# CDST_final_PCB_v1_0.net
KiCad netlist of a schematic drawn in EAGLE
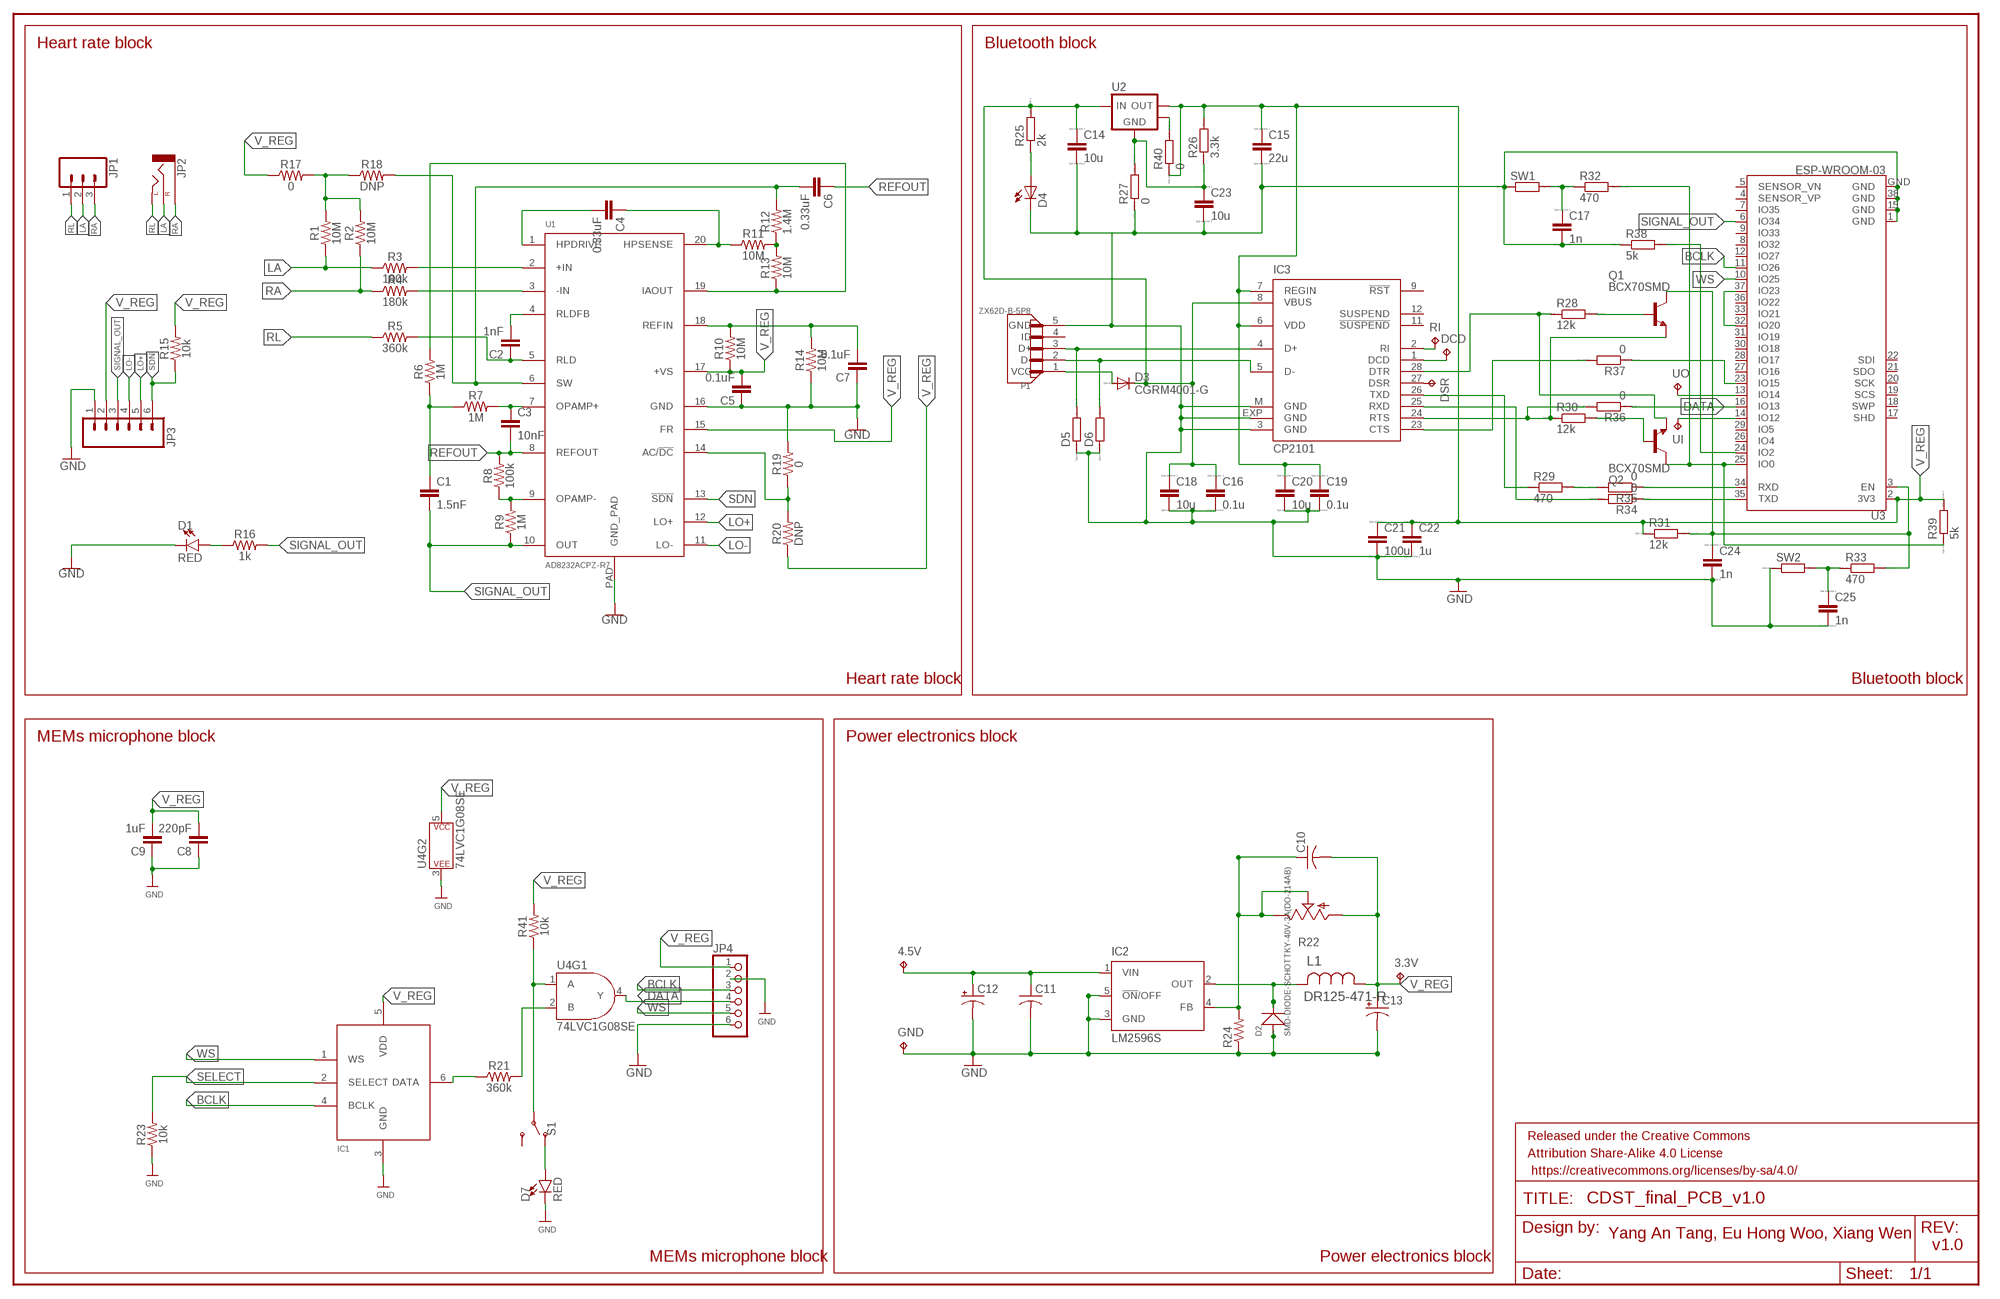
[diagram p0: schematic, sheet 1]

(export (version "E")
  (design (tool "Eeschema 10.0.6"))
  (components
    (comp (ref "3.3V")
      (value "TPTP20SQ")
      (footprint "eagle-import:TP20SQ")
      (libsource (lib "eagle-import") (part "TPTP20SQ"))
    )
    (comp (ref "4.5V")
      (value "TPTP20SQ")
      (footprint "eagle-import:TP20SQ")
      (libsource (lib "eagle-import") (part "TPTP20SQ"))
    )
    (comp (ref "C1")
      (value "1.5nF")
      (footprint "eagle-import:C1206")
      (libsource (lib "eagle-import") (part "C-EUC1206"))
    )
    (comp (ref "C2")
      (value "1nF")
      (footprint "eagle-import:C1206")
      (libsource (lib "eagle-import") (part "C-EUC1206"))
    )
    (comp (ref "C3")
      (value "10nF")
      (footprint "eagle-import:C1206")
      (libsource (lib "eagle-import") (part "C-EUC1206"))
    )
    (comp (ref "C4")
      (value "0.33uF")
      (footprint "eagle-import:C1206")
      (libsource (lib "eagle-import") (part "C-EUC1206"))
    )
    (comp (ref "C5")
      (value "0.1uF")
      (footprint "eagle-import:C1206")
      (libsource (lib "eagle-import") (part "C-EUC1206"))
    )
    (comp (ref "C6")
      (value "0.33uF")
      (footprint "eagle-import:C1206")
      (libsource (lib "eagle-import") (part "C-EUC1206"))
    )
    (comp (ref "C7")
      (value "0.1uF")
      (footprint "eagle-import:C1206")
      (libsource (lib "eagle-import") (part "C-EUC1206"))
    )
    (comp (ref "C8")
      (value "220pF")
      (footprint "eagle-import:C1206")
      (libsource (lib "eagle-import") (part "C-EUC1206"))
    )
    (comp (ref "C9")
      (value "1uF")
      (footprint "eagle-import:C1206")
      (libsource (lib "eagle-import") (part "C-EUC1206"))
    )
    (comp (ref "C10")
      (value "C-USC0402")
      (footprint "eagle-import:C0402")
      (libsource (lib "eagle-import") (part "C-USC0402"))
    )
    (comp (ref "C11")
      (value "C-USC0402")
      (footprint "eagle-import:C0402")
      (libsource (lib "eagle-import") (part "C-USC0402"))
    )
    (comp (ref "C12")
      (value "CPOL-USSANYO_SMD_F8")
      (footprint "eagle-import:SANYO-OSCON_SMD_F8")
      (libsource (lib "eagle-import") (part "CPOL-USSANYO_SMD_F8"))
    )
    (comp (ref "C13")
      (value "CPOL-USSANYO_SMD_F8")
      (footprint "eagle-import:SANYO-OSCON_SMD_F8")
      (libsource (lib "eagle-import") (part "CPOL-USSANYO_SMD_F8"))
    )
    (comp (ref "C14")
      (value "10u")
      (footprint "eagle-import:C1206")
      (libsource (lib "eagle-import") (part "CC1206"))
    )
    (comp (ref "C15")
      (value "22u")
      (footprint "eagle-import:C1206")
      (libsource (lib "eagle-import") (part "CC1206"))
    )
    (comp (ref "C16")
      (value "0.1u")
      (footprint "eagle-import:C1206")
      (libsource (lib "eagle-import") (part "CC1206"))
    )
    (comp (ref "C17")
      (value "1n")
      (footprint "eagle-import:C1206")
      (libsource (lib "eagle-import") (part "CC1206"))
    )
    (comp (ref "C18")
      (value "10u")
      (footprint "eagle-import:C1206")
      (libsource (lib "eagle-import") (part "CC1206"))
    )
    (comp (ref "C19")
      (value "0.1u")
      (footprint "eagle-import:C1206")
      (libsource (lib "eagle-import") (part "CC1206"))
    )
    (comp (ref "C20")
      (value "10u")
      (footprint "eagle-import:C1206")
      (libsource (lib "eagle-import") (part "CC1206"))
    )
    (comp (ref "C21")
      (value "100u")
      (footprint "eagle-import:C1206")
      (libsource (lib "eagle-import") (part "CC1206"))
    )
    (comp (ref "C22")
      (value "1u")
      (footprint "eagle-import:C1206")
      (libsource (lib "eagle-import") (part "CC1206"))
    )
    (comp (ref "C23")
      (value "10u")
      (footprint "eagle-import:C1206")
      (libsource (lib "eagle-import") (part "CC1206"))
    )
    (comp (ref "C24")
      (value "1n")
      (footprint "eagle-import:C1206")
      (libsource (lib "eagle-import") (part "CC1206"))
    )
    (comp (ref "C25")
      (value "1n")
      (footprint "eagle-import:C1206")
      (libsource (lib "eagle-import") (part "CC1206"))
    )
    (comp (ref "D1")
      (value "RED")
      (footprint "eagle-import:LED-1206")
      (libsource (lib "eagle-import") (part "LED-RED1206"))
    )
    (comp (ref "D2")
      (value "SMD-DIODE-SCHOTTKY-40V-3A(DO-214AB)")
      (footprint "eagle-import:DO-214AB")
      (fields (field (name "MF") "Vishay") (field (name "MP") "SS34-E3/57T"))
      (libsource (lib "eagle-import") (part "SMD-DIODE-SCHOTTKY-40V-3A(DO-214AB)"))
    )
    (comp (ref "D3")
      (value "CGRM4001-G")
      (footprint "eagle-import:SOD-123_MINI-SMA")
      (libsource (lib "eagle-import") (part "CGRM400-G1"))
    )
    (comp (ref "D4")
      (value "LEDCHIPLED_0805")
      (footprint "eagle-import:CHIPLED_0805")
      (libsource (lib "eagle-import") (part "LEDCHIPLED_0805"))
    )
    (comp (ref "D5")
      (value "RR0402")
      (footprint "eagle-import:R0402")
      (libsource (lib "eagle-import") (part "RR0402"))
    )
    (comp (ref "D6")
      (value "RR0402")
      (footprint "eagle-import:R0402")
      (libsource (lib "eagle-import") (part "RR0402"))
    )
    (comp (ref "D7")
      (value "RED")
      (footprint "eagle-import:LED-1206")
      (libsource (lib "eagle-import") (part "LED-RED1206"))
    )
    (comp (ref "DCD")
      (value "TPB2,54")
      (footprint "eagle-import:B2,54")
      (libsource (lib "eagle-import") (part "testpad_385_TPB2,54"))
    )
    (comp (ref "DSR")
      (value "TPB2,54")
      (footprint "eagle-import:B2,54")
      (libsource (lib "eagle-import") (part "testpad_385_TPB2,54"))
    )
    (comp (ref "FRAME1")
      (value "FRAME-LEDGER")
      (footprint "eagle-import:CREATIVE_COMMONS")
      (libsource (lib "eagle-import") (part "FRAME-LEDGER"))
    )
    (comp (ref "GND")
      (value "TPTP20SQ")
      (footprint "eagle-import:TP20SQ")
      (libsource (lib "eagle-import") (part "TPTP20SQ"))
    )
    (comp (ref "IC1")
      (value "MIC_I2S_SPH0645")
      (footprint "eagle-import:SPH0645LM4H")
      (libsource (lib "eagle-import") (part "MIC_I2S_SPH0645"))
    )
    (comp (ref "IC2")
      (value "LM2596S")
      (footprint "eagle-import:TO263-5")
      (fields (field (name "MF") "NATIONAL SEMICONDUCTOR") (field (name "MPN") "LM2596S-ADJ/NOPB"))
      (libsource (lib "eagle-import") (part "LM2596S"))
    )
    (comp (ref "IC3")
      (value "CP2101")
      (footprint "eagle-import:MLP28")
      (fields (field (name "MF") "FARNELL") (field (name "MPN") "CP2102-GM"))
      (libsource (lib "eagle-import") (part "CP2101"))
    )
    (comp (ref "JP1")
      (value "M03PTH")
      (footprint "eagle-import:1X03")
      (libsource (lib "eagle-import") (part "M03PTH"))
    )
    (comp (ref "JP2")
      (value "AUDIO-JACKSMD2")
      (footprint "eagle-import:AUDIO-JACK-3.5MM-SMD")
      (libsource (lib "eagle-import") (part "AUDIO-JACKSMD2"))
    )
    (comp (ref "JP3")
      (value "M06SIP")
      (footprint "eagle-import:1X06")
      (libsource (lib "eagle-import") (part "M06SIP"))
    )
    (comp (ref "JP4")
      (value "HEADER-1X6ROUND")
      (footprint "eagle-import:1X06_ROUND")
      (libsource (lib "eagle-import") (part "HEADER-1X6ROUND"))
    )
    (comp (ref "L1")
      (value "DR125-471-R")
      (footprint "eagle-import:INDM125125X600N")
      (fields (field (name "MF") "Cooper Bussmann"))
      (libsource (lib "eagle-import") (part "DR125-471-R"))
    )
    (comp (ref "P1")
      (value "ZX62D-B-5P8")
      (footprint "eagle-import:HRS_ZX62D-B-5P8")
      (fields (field (name "MF") "Hirose"))
      (libsource (lib "eagle-import") (part "ZX62D-B-5P8"))
    )
    (comp (ref "Q1")
      (value "BCX70SMD")
      (footprint "eagle-import:SOT23")
      (libsource (lib "eagle-import") (part "BCX70SMD"))
    )
    (comp (ref "Q2")
      (value "BCX70SMD")
      (footprint "eagle-import:SOT23")
      (libsource (lib "eagle-import") (part "BCX70SMD"))
    )
    (comp (ref "R1")
      (value "10M")
      (footprint "eagle-import:1206")
      (libsource (lib "eagle-import") (part "RESISTOR1206"))
    )
    (comp (ref "R2")
      (value "10M")
      (footprint "eagle-import:1206")
      (libsource (lib "eagle-import") (part "RESISTOR1206"))
    )
    (comp (ref "R3")
      (value "180k")
      (footprint "eagle-import:1206")
      (libsource (lib "eagle-import") (part "RESISTOR1206"))
    )
    (comp (ref "R4")
      (value "180k")
      (footprint "eagle-import:1206")
      (libsource (lib "eagle-import") (part "RESISTOR1206"))
    )
    (comp (ref "R5")
      (value "360k")
      (footprint "eagle-import:1206")
      (libsource (lib "eagle-import") (part "RESISTOR1206"))
    )
    (comp (ref "R6")
      (value "1M")
      (footprint "eagle-import:1206")
      (libsource (lib "eagle-import") (part "RESISTOR1206"))
    )
    (comp (ref "R7")
      (value "1M")
      (footprint "eagle-import:1206")
      (libsource (lib "eagle-import") (part "RESISTOR1206"))
    )
    (comp (ref "R8")
      (value "100k")
      (footprint "eagle-import:1206")
      (libsource (lib "eagle-import") (part "RESISTOR1206"))
    )
    (comp (ref "R9")
      (value "1M")
      (footprint "eagle-import:1206")
      (libsource (lib "eagle-import") (part "RESISTOR1206"))
    )
    (comp (ref "R10")
      (value "10M")
      (footprint "eagle-import:1206")
      (libsource (lib "eagle-import") (part "RESISTOR1206"))
    )
    (comp (ref "R11")
      (value "10M")
      (footprint "eagle-import:1206")
      (libsource (lib "eagle-import") (part "RESISTOR1206"))
    )
    (comp (ref "R12")
      (value "1.4M")
      (footprint "eagle-import:1206")
      (libsource (lib "eagle-import") (part "RESISTOR1206"))
    )
    (comp (ref "R13")
      (value "10M")
      (footprint "eagle-import:1206")
      (libsource (lib "eagle-import") (part "RESISTOR1206"))
    )
    (comp (ref "R14")
      (value "10M")
      (footprint "eagle-import:1206")
      (libsource (lib "eagle-import") (part "RESISTOR1206"))
    )
    (comp (ref "R15")
      (value "10k")
      (footprint "eagle-import:1206")
      (libsource (lib "eagle-import") (part "RESISTOR1206"))
    )
    (comp (ref "R16")
      (value "1k")
      (footprint "eagle-import:1206")
      (libsource (lib "eagle-import") (part "RESISTOR1206"))
    )
    (comp (ref "R17")
      (value "0")
      (footprint "eagle-import:1206")
      (libsource (lib "eagle-import") (part "RESISTOR1206"))
    )
    (comp (ref "R18")
      (value "DNP")
      (footprint "eagle-import:1206")
      (libsource (lib "eagle-import") (part "RESISTOR1206"))
    )
    (comp (ref "R19")
      (value "0")
      (footprint "eagle-import:1206")
      (libsource (lib "eagle-import") (part "RESISTOR1206"))
    )
    (comp (ref "R20")
      (value "DNP")
      (footprint "eagle-import:1206")
      (libsource (lib "eagle-import") (part "RESISTOR1206"))
    )
    (comp (ref "R21")
      (value "360k")
      (footprint "eagle-import:1206")
      (libsource (lib "eagle-import") (part "RESISTOR1206"))
    )
    (comp (ref "R22")
      (value "TRIM_US-RJ9W")
      (footprint "eagle-import:RJ9W")
      (libsource (lib "eagle-import") (part "TRIM_US-RJ9W"))
    )
    (comp (ref "R23")
      (value "10k")
      (footprint "eagle-import:1206")
      (libsource (lib "eagle-import") (part "RESISTOR1206"))
    )
    (comp (ref "R24")
      (value "R-US_MELF0204W")
      (footprint "eagle-import:MINI_MELF-0204W")
      (libsource (lib "eagle-import") (part "R-US_MELF0204W"))
    )
    (comp (ref "R25")
      (value "2k")
      (footprint "eagle-import:R1206")
      (libsource (lib "eagle-import") (part "RR1206"))
    )
    (comp (ref "R26")
      (value "3.3k")
      (footprint "eagle-import:R1206")
      (libsource (lib "eagle-import") (part "RR1206"))
    )
    (comp (ref "R27")
      (value "0")
      (footprint "eagle-import:R1206")
      (libsource (lib "eagle-import") (part "RR1206"))
    )
    (comp (ref "R28")
      (value "12k")
      (footprint "eagle-import:R1206")
      (libsource (lib "eagle-import") (part "RR1206"))
    )
    (comp (ref "R29")
      (value "470")
      (footprint "eagle-import:R1206")
      (libsource (lib "eagle-import") (part "RR1206"))
    )
    (comp (ref "R30")
      (value "12k")
      (footprint "eagle-import:R1206")
      (libsource (lib "eagle-import") (part "RR1206"))
    )
    (comp (ref "R31")
      (value "12k")
      (footprint "eagle-import:R1206")
      (libsource (lib "eagle-import") (part "RR1206"))
    )
    (comp (ref "R32")
      (value "470")
      (footprint "eagle-import:R1206")
      (libsource (lib "eagle-import") (part "RR1206"))
    )
    (comp (ref "R33")
      (value "470")
      (footprint "eagle-import:R1206")
      (libsource (lib "eagle-import") (part "RR1206"))
    )
    (comp (ref "R34")
      (value "0")
      (footprint "eagle-import:R1206")
      (libsource (lib "eagle-import") (part "RR1206"))
    )
    (comp (ref "R35")
      (value "0")
      (footprint "eagle-import:R1206")
      (libsource (lib "eagle-import") (part "RR1206"))
    )
    (comp (ref "R36")
      (value "0")
      (footprint "eagle-import:R1206")
      (libsource (lib "eagle-import") (part "RR1206"))
    )
    (comp (ref "R37")
      (value "0")
      (footprint "eagle-import:R1206")
      (libsource (lib "eagle-import") (part "RR1206"))
    )
    (comp (ref "R38")
      (value "5k")
      (footprint "eagle-import:R1206")
      (libsource (lib "eagle-import") (part "RR1206"))
    )
    (comp (ref "R39")
      (value "5k")
      (footprint "eagle-import:R1206")
      (libsource (lib "eagle-import") (part "RR1206"))
    )
    (comp (ref "R40")
      (value "0")
      (footprint "eagle-import:R1206")
      (libsource (lib "eagle-import") (part "RR1206"))
    )
    (comp (ref "R41")
      (value "10k")
      (footprint "eagle-import:1206")
      (libsource (lib "eagle-import") (part "RESISTOR1206"))
    )
    (comp (ref "RI")
      (value "TPB2,54")
      (footprint "eagle-import:B2,54")
      (libsource (lib "eagle-import") (part "testpad_385_TPB2,54"))
    )
    (comp (ref "S1")
      (value "SWITCH-SPDT-SMD-RIGHT-ANGLE")
      (footprint "eagle-import:SWITCH_SPST_SMD_A")
      (libsource (lib "eagle-import") (part "SWITCH-SPDT-SMD-RIGHT-ANGLE"))
    )
    (comp (ref "SW1")
      (value "RR2010")
      (footprint "eagle-import:R2010")
      (libsource (lib "eagle-import") (part "RR2010"))
    )
    (comp (ref "SW2")
      (value "RR2010")
      (footprint "eagle-import:R2010")
      (libsource (lib "eagle-import") (part "RR2010"))
    )
    (comp (ref "U1")
      (value "AD8232ACPZ-R7")
      (footprint "eagle-import:LFCSP_20")
      (libsource (lib "eagle-import") (part "AD8232"))
    )
    (comp (ref "U2")
      (value "LM1117-SOT223")
      (footprint "eagle-import:SOT-223-3")
      (libsource (lib "eagle-import") (part "LM1117-SOT223"))
    )
    (comp (ref "U3")
      (value "ESP-WROOM-03")
      (footprint "eagle-import:ESP-WROOM-03")
      (libsource (lib "eagle-import") (part "ESP-WROOM-03"))
    )
    (comp (ref "U4")
      (value "74LVC1G08SE")
      (footprint "eagle-import:SOT23-5")
      (libsource (lib "eagle-import") (part "7408SELVC"))
    )
    (comp (ref "UI")
      (value "TPB1,27")
      (footprint "eagle-import:B1,27")
      (libsource (lib "eagle-import") (part "testpad_385_TPB1,27"))
    )
    (comp (ref "UO")
      (value "TPB1,27")
      (footprint "eagle-import:B1,27")
      (libsource (lib "eagle-import") (part "testpad_385_TPB1,27"))
    )
  )
  (nets
    (net (code "1") (name "BCLK") (class "Default")
      (node (ref "IC1") (pin "4") (pinfunction "BCLK_4") (pintype "input"))
      (node (ref "JP4") (pin "3") (pinfunction "3_3") (pintype "passive"))
      (node (ref "U3") (pin "11") (pinfunction "IO26_11") (pintype "bidirectional"))
    )
    (net (code "2") (name "DATA") (class "Default")
      (node (ref "JP4") (pin "4") (pinfunction "4_4") (pintype "passive"))
      (node (ref "R36") (pin "1") (pinfunction "1_1") (pintype "passive"))
      (node (ref "U3") (pin "16") (pinfunction "IO13_16") (pintype "bidirectional"))
      (node (ref "U4") (pin "4") (pinfunction "Y_4") (pintype "bidirectional"))
    )
    (net (code "3") (name "GND") (class "Default")
      (node (ref "C11") (pin "2") (pinfunction "2_2") (pintype "passive"))
      (node (ref "C12") (pin "-") (pinfunction "-_-") (pintype "passive"))
      (node (ref "C13") (pin "-") (pinfunction "-_-") (pintype "passive"))
      (node (ref "C14") (pin "2") (pinfunction "2_2") (pintype "passive"))
      (node (ref "C15") (pin "2") (pinfunction "2_2") (pintype "passive"))
      (node (ref "C16") (pin "2") (pinfunction "2_2") (pintype "passive"))
      (node (ref "C17") (pin "2") (pinfunction "2_2") (pintype "passive"))
      (node (ref "C18") (pin "2") (pinfunction "2_2") (pintype "passive"))
      (node (ref "C19") (pin "2") (pinfunction "2_2") (pintype "passive"))
      (node (ref "C20") (pin "2") (pinfunction "2_2") (pintype "passive"))
      (node (ref "C21") (pin "2") (pinfunction "2_2") (pintype "passive"))
      (node (ref "C22") (pin "2") (pinfunction "2_2") (pintype "passive"))
      (node (ref "C23") (pin "1") (pinfunction "1_1") (pintype "passive"))
      (node (ref "C23") (pin "2") (pinfunction "2_2") (pintype "passive"))
      (node (ref "C24") (pin "2") (pinfunction "2_2") (pintype "passive"))
      (node (ref "C25") (pin "2") (pinfunction "2_2") (pintype "passive"))
      (node (ref "C5") (pin "1") (pinfunction "1_1") (pintype "passive"))
      (node (ref "C7") (pin "1") (pinfunction "1_1") (pintype "passive"))
      (node (ref "C8") (pin "1") (pinfunction "1_1") (pintype "passive"))
      (node (ref "C9") (pin "1") (pinfunction "1_1") (pintype "passive"))
      (node (ref "D1") (pin "C") (pinfunction "C_C") (pintype "passive"))
      (node (ref "D2") (pin "1") (pinfunction "+_1") (pintype "passive"))
      (node (ref "D4") (pin "C") (pinfunction "C_C") (pintype "passive"))
      (node (ref "D5") (pin "1") (pinfunction "1_1") (pintype "passive"))
      (node (ref "D6") (pin "1") (pinfunction "1_1") (pintype "passive"))
      (node (ref "D7") (pin "C") (pinfunction "C_C") (pintype "passive"))
      (node (ref "GND") (pin "TP") (pinfunction "TP_TP") (pintype "input"))
      (node (ref "IC1") (pin "3") (pinfunction "GND_3") (pintype "power_in"))
      (node (ref "IC2") (pin "3") (pinfunction "GND_3") (pintype "power_in"))
      (node (ref "IC2") (pin "5") (pinfunction "~{ON}/OFF_5") (pintype "input"))
      (node (ref "IC3") (pin "3") (pinfunction "GND_3") (pintype "power_in"))
      (node (ref "IC3") (pin "EXP") (pinfunction "GND_EXP") (pintype "power_in"))
      (node (ref "IC3") (pin "M") (pinfunction "GND_M") (pintype "power_in"))
      (node (ref "JP3") (pin "1") (pinfunction "1_1") (pintype "passive"))
      (node (ref "JP4") (pin "2") (pinfunction "2_2") (pintype "passive"))
      (node (ref "JP4") (pin "6") (pinfunction "6_6") (pintype "passive"))
      (node (ref "P1") (pin "5") (pinfunction "GND_5") (pintype "power_in"))
      (node (ref "R14") (pin "1") (pinfunction "1_1") (pintype "passive"))
      (node (ref "R19") (pin "2") (pinfunction "2_2") (pintype "passive"))
      (node (ref "R23") (pin "1") (pinfunction "1_1") (pintype "passive"))
      (node (ref "R24") (pin "1") (pinfunction "1_1") (pintype "passive"))
      (node (ref "R26") (pin "1") (pinfunction "1_1") (pintype "passive"))
      (node (ref "R27") (pin "1") (pinfunction "1_1") (pintype "passive"))
      (node (ref "R27") (pin "2") (pinfunction "2_2") (pintype "passive"))
      (node (ref "R38") (pin "1") (pinfunction "1_1") (pintype "passive"))
      (node (ref "SW1") (pin "1") (pinfunction "1_1") (pintype "passive"))
      (node (ref "SW2") (pin "1") (pinfunction "1_1") (pintype "passive"))
      (node (ref "U1") (pin "16") (pinfunction "GND_16") (pintype "bidirectional"))
      (node (ref "U1") (pin "PAD") (pinfunction "GND_PAD_PAD") (pintype "bidirectional"))
      (node (ref "U2") (pin "1") (pinfunction "GND_1") (pintype "power_in"))
      (node (ref "U3") (pin "1") (pinfunction "GND_1") (pintype "bidirectional"))
      (node (ref "U3") (pin "15") (pinfunction "GND_15") (pintype "bidirectional"))
      (node (ref "U3") (pin "38") (pinfunction "GND_38") (pintype "bidirectional"))
      (node (ref "U3") (pin "GND") (pinfunction "GND_GND") (pintype "bidirectional"))
      (node (ref "U4") (pin "3") (pinfunction "P$V-_3") (pintype "bidirectional"))
    )
    (net (code "4") (name "LA") (class "Default")
      (node (ref "JP1") (pin "2") (pinfunction "2_2") (pintype "passive"))
      (node (ref "JP2") (pin "RING") (pinfunction "RIGHT_RING") (pintype "bidirectional"))
      (node (ref "R1") (pin "1") (pinfunction "1_1") (pintype "passive"))
      (node (ref "R3") (pin "1") (pinfunction "1_1") (pintype "passive"))
    )
    (net (code "5") (name "LO+") (class "Default")
      (node (ref "JP3") (pin "5") (pinfunction "5_5") (pintype "passive"))
      (node (ref "U1") (pin "12") (pinfunction "LO+_12") (pintype "bidirectional"))
    )
    (net (code "6") (name "LO-") (class "Default")
      (node (ref "JP3") (pin "4") (pinfunction "4_4") (pintype "passive"))
      (node (ref "U1") (pin "11") (pinfunction "LO-_11") (pintype "bidirectional"))
    )
    (net (code "7") (name "Net-(C1-Pad1)") (class "Default")
      (node (ref "C1") (pin "1") (pinfunction "1_1") (pintype "passive"))
      (node (ref "R6") (pin "1") (pinfunction "1_1") (pintype "passive"))
      (node (ref "R7") (pin "1") (pinfunction "1_1") (pintype "passive"))
    )
    (net (code "8") (name "Net-(C17-Pad1)") (class "Default")
      (node (ref "C17") (pin "1") (pinfunction "1_1") (pintype "passive"))
      (node (ref "R32") (pin "1") (pinfunction "1_1") (pintype "passive"))
      (node (ref "SW1") (pin "2") (pinfunction "2_2") (pintype "passive"))
    )
    (net (code "9") (name "Net-(C25-Pad1)") (class "Default")
      (node (ref "C25") (pin "1") (pinfunction "1_1") (pintype "passive"))
      (node (ref "R33") (pin "1") (pinfunction "1_1") (pintype "passive"))
      (node (ref "SW2") (pin "2") (pinfunction "2_2") (pintype "passive"))
    )
    (net (code "10") (name "Net-(D1-PadA)") (class "Default")
      (node (ref "D1") (pin "A") (pinfunction "A_A") (pintype "passive"))
      (node (ref "R16") (pin "1") (pinfunction "1_1") (pintype "passive"))
    )
    (net (code "11") (name "Net-(D2--)") (class "Default")
      (node (ref "D2") (pin "2") (pinfunction "-_2") (pintype "passive"))
      (node (ref "IC2") (pin "2") (pinfunction "OUT_2") (pintype "output"))
      (node (ref "L1") (pin "2") (pinfunction "2_2") (pintype "passive"))
    )
    (net (code "12") (name "Net-(D4-PadA)") (class "Default")
      (node (ref "D4") (pin "A") (pinfunction "A_A") (pintype "passive"))
      (node (ref "R25") (pin "1") (pinfunction "1_1") (pintype "passive"))
    )
    (net (code "13") (name "Net-(IC1-DATA)") (class "Default")
      (node (ref "IC1") (pin "6") (pinfunction "DATA_6") (pintype "output"))
      (node (ref "R21") (pin "1") (pinfunction "1_1") (pintype "passive"))
    )
    (net (code "14") (name "Net-(IC2-FB)") (class "Default")
      (node (ref "C10") (pin "1") (pinfunction "1_1") (pintype "passive"))
      (node (ref "IC2") (pin "4") (pinfunction "FB_4") (pintype "input"))
      (node (ref "R22") (pin "E") (pinfunction "E_E") (pintype "passive"))
      (node (ref "R22") (pin "S") (pinfunction "S_S") (pintype "passive"))
      (node (ref "R24") (pin "2") (pinfunction "2_2") (pintype "passive"))
    )
    (net (code "15") (name "Net-(IC2-VIN)") (class "Default")
      (node (ref "4.5V") (pin "TP") (pinfunction "TP_TP") (pintype "input"))
      (node (ref "C11") (pin "1") (pinfunction "1_1") (pintype "passive"))
      (node (ref "C12") (pin "+") (pinfunction "+_+") (pintype "passive"))
      (node (ref "IC2") (pin "1") (pinfunction "VIN_1") (pintype "input"))
    )
    (net (code "16") (name "Net-(IC3-CTS)") (class "Default")
      (node (ref "IC3") (pin "23") (pinfunction "CTS_23") (pintype "input"))
      (node (ref "R37") (pin "2") (pinfunction "2_2") (pintype "passive"))
    )
    (net (code "17") (name "Net-(IC3-D+)") (class "Default")
      (node (ref "D5") (pin "2") (pinfunction "2_2") (pintype "passive"))
      (node (ref "IC3") (pin "4") (pinfunction "D+_4") (pintype "bidirectional"))
      (node (ref "P1") (pin "3") (pinfunction "D+_3") (pintype "passive"))
    )
    (net (code "18") (name "Net-(IC3-D-)") (class "Default")
      (node (ref "D6") (pin "2") (pinfunction "2_2") (pintype "passive"))
      (node (ref "IC3") (pin "5") (pinfunction "D-_5") (pintype "bidirectional"))
      (node (ref "P1") (pin "2") (pinfunction "D-_2") (pintype "passive"))
    )
    (net (code "19") (name "Net-(IC3-DCD)") (class "Default")
      (node (ref "DCD") (pin "TP") (pinfunction "TP_TP") (pintype "input"))
      (node (ref "IC3") (pin "1") (pinfunction "DCD_1") (pintype "input"))
    )
    (net (code "20") (name "Net-(IC3-DSR)") (class "Default")
      (node (ref "DSR") (pin "TP") (pinfunction "TP_TP") (pintype "input"))
      (node (ref "IC3") (pin "27") (pinfunction "DSR_27") (pintype "input"))
    )
    (net (code "21") (name "Net-(IC3-DTR)") (class "Default")
      (node (ref "IC3") (pin "28") (pinfunction "DTR_28") (pintype "output"))
      (node (ref "Q2") (pin "2") (pinfunction "E_2") (pintype "passive"))
      (node (ref "R28") (pin "1") (pinfunction "1_1") (pintype "passive"))
    )
    (net (code "22") (name "Net-(IC3-RI)") (class "Default")
      (node (ref "IC3") (pin "2") (pinfunction "RI_2") (pintype "input"))
      (node (ref "RI") (pin "TP") (pinfunction "TP_TP") (pintype "input"))
    )
    (net (code "23") (name "Net-(IC3-RTS)") (class "Default")
      (node (ref "IC3") (pin "24") (pinfunction "RTS_24") (pintype "output"))
      (node (ref "Q1") (pin "2") (pinfunction "E_2") (pintype "passive"))
      (node (ref "R30") (pin "1") (pinfunction "1_1") (pintype "passive"))
      (node (ref "R36") (pin "2") (pinfunction "2_2") (pintype "passive"))
    )
    (net (code "24") (name "Net-(IC3-RXD)") (class "Default")
      (node (ref "IC3") (pin "25") (pinfunction "RXD_25") (pintype "input"))
      (node (ref "R34") (pin "2") (pinfunction "2_2") (pintype "passive"))
    )
    (net (code "25") (name "Net-(IC3-TXD)") (class "Default")
      (node (ref "IC3") (pin "26") (pinfunction "TXD_26") (pintype "output"))
      (node (ref "R29") (pin "1") (pinfunction "1_1") (pintype "passive"))
    )
    (net (code "26") (name "Net-(IC3-VBUS)") (class "Default")
      (node (ref "C14") (pin "1") (pinfunction "1_1") (pintype "passive"))
      (node (ref "C16") (pin "1") (pinfunction "1_1") (pintype "passive"))
      (node (ref "C18") (pin "1") (pinfunction "1_1") (pintype "passive"))
      (node (ref "D3") (pin "C") (pinfunction "C_C") (pintype "passive"))
      (node (ref "IC3") (pin "8") (pinfunction "VBUS_8") (pintype "input"))
      (node (ref "R25") (pin "2") (pinfunction "2_2") (pintype "passive"))
      (node (ref "U2") (pin "3") (pinfunction "VIN_3") (pintype "power_in"))
    )
    (net (code "27") (name "Net-(P1-VCC)") (class "Default")
      (node (ref "D3") (pin "A") (pinfunction "A_A") (pintype "passive"))
      (node (ref "P1") (pin "1") (pinfunction "VCC_1") (pintype "power_in"))
    )
    (net (code "28") (name "Net-(Q1-B)") (class "Default")
      (node (ref "Q1") (pin "1") (pinfunction "B_1") (pintype "passive"))
      (node (ref "R28") (pin "2") (pinfunction "2_2") (pintype "passive"))
    )
    (net (code "29") (name "Net-(Q1-C)") (class "Default")
      (node (ref "C24") (pin "1") (pinfunction "1_1") (pintype "passive"))
      (node (ref "Q1") (pin "3") (pinfunction "C_3") (pintype "passive"))
      (node (ref "R31") (pin "2") (pinfunction "2_2") (pintype "passive"))
      (node (ref "R33") (pin "2") (pinfunction "2_2") (pintype "passive"))
      (node (ref "U3") (pin "3") (pinfunction "EN_3") (pintype "bidirectional"))
    )
    (net (code "30") (name "Net-(Q2-B)") (class "Default")
      (node (ref "Q2") (pin "1") (pinfunction "B_1") (pintype "passive"))
      (node (ref "R30") (pin "2") (pinfunction "2_2") (pintype "passive"))
    )
    (net (code "31") (name "Net-(Q2-C)") (class "Default")
      (node (ref "Q2") (pin "3") (pinfunction "C_3") (pintype "passive"))
      (node (ref "R32") (pin "2") (pinfunction "2_2") (pintype "passive"))
      (node (ref "R39") (pin "1") (pinfunction "1_1") (pintype "passive"))
      (node (ref "U3") (pin "25") (pinfunction "IO0_25") (pintype "bidirectional"))
    )
    (net (code "32") (name "Net-(R1-Pad2)") (class "Default")
      (node (ref "R1") (pin "2") (pinfunction "2_2") (pintype "passive"))
      (node (ref "R17") (pin "2") (pinfunction "2_2") (pintype "passive"))
      (node (ref "R18") (pin "1") (pinfunction "1_1") (pintype "passive"))
      (node (ref "R2") (pin "2") (pinfunction "2_2") (pintype "passive"))
    )
    (net (code "33") (name "Net-(R11-Pad2)") (class "Default")
      (node (ref "R11") (pin "2") (pinfunction "2_2") (pintype "passive"))
      (node (ref "R12") (pin "1") (pinfunction "1_1") (pintype "passive"))
      (node (ref "R13") (pin "2") (pinfunction "2_2") (pintype "passive"))
    )
    (net (code "34") (name "Net-(R29-Pad2)") (class "Default")
      (node (ref "R29") (pin "2") (pinfunction "2_2") (pintype "passive"))
      (node (ref "R35") (pin "2") (pinfunction "2_2") (pintype "passive"))
    )
    (net (code "35") (name "Net-(S1-O)") (class "Default")
      (node (ref "D7") (pin "A") (pinfunction "A_A") (pintype "passive"))
      (node (ref "S1") (pin "1") (pinfunction "O_1") (pintype "passive"))
    )
    (net (code "36") (name "Net-(S1-P)") (class "Default")
      (node (ref "R41") (pin "1") (pinfunction "1_1") (pintype "passive"))
      (node (ref "S1") (pin "2") (pinfunction "P_2") (pintype "passive"))
      (node (ref "U4") (pin "1") (pinfunction "A_1") (pintype "bidirectional"))
    )
    (net (code "37") (name "Net-(U1-+IN)") (class "Default")
      (node (ref "R3") (pin "2") (pinfunction "2_2") (pintype "passive"))
      (node (ref "U1") (pin "2") (pinfunction "+IN_2") (pintype "bidirectional"))
    )
    (net (code "38") (name "Net-(U1--IN)") (class "Default")
      (node (ref "R4") (pin "2") (pinfunction "2_2") (pintype "passive"))
      (node (ref "U1") (pin "3") (pinfunction "-IN_3") (pintype "bidirectional"))
    )
    (net (code "39") (name "Net-(U1-AC{slash}~{DC})") (class "Default")
      (node (ref "R19") (pin "1") (pinfunction "1_1") (pintype "passive"))
      (node (ref "R20") (pin "2") (pinfunction "2_2") (pintype "passive"))
      (node (ref "U1") (pin "14") (pinfunction "AC/~{DC}_14") (pintype "bidirectional"))
    )
    (net (code "40") (name "Net-(U1-HPDRIVE)") (class "Default")
      (node (ref "C4") (pin "2") (pinfunction "2_2") (pintype "passive"))
      (node (ref "U1") (pin "1") (pinfunction "HPDRIVE_1") (pintype "bidirectional"))
    )
    (net (code "41") (name "Net-(U1-HPSENSE)") (class "Default")
      (node (ref "C4") (pin "1") (pinfunction "1_1") (pintype "passive"))
      (node (ref "R11") (pin "1") (pinfunction "1_1") (pintype "passive"))
      (node (ref "U1") (pin "20") (pinfunction "HPSENSE_20") (pintype "bidirectional"))
    )
    (net (code "42") (name "Net-(U1-IAOUT)") (class "Default")
      (node (ref "R13") (pin "1") (pinfunction "1_1") (pintype "passive"))
      (node (ref "R6") (pin "2") (pinfunction "2_2") (pintype "passive"))
      (node (ref "U1") (pin "19") (pinfunction "IAOUT_19") (pintype "bidirectional"))
    )
    (net (code "43") (name "Net-(U1-OPAMP+)") (class "Default")
      (node (ref "C3") (pin "1") (pinfunction "1_1") (pintype "passive"))
      (node (ref "R7") (pin "2") (pinfunction "2_2") (pintype "passive"))
      (node (ref "U1") (pin "7") (pinfunction "OPAMP+_7") (pintype "bidirectional"))
    )
    (net (code "44") (name "Net-(U1-OPAMP-)") (class "Default")
      (node (ref "R8") (pin "1") (pinfunction "1_1") (pintype "passive"))
      (node (ref "R9") (pin "2") (pinfunction "2_2") (pintype "passive"))
      (node (ref "U1") (pin "9") (pinfunction "OPAMP-_9") (pintype "bidirectional"))
    )
    (net (code "45") (name "Net-(U1-REFIN)") (class "Default")
      (node (ref "C7") (pin "2") (pinfunction "2_2") (pintype "passive"))
      (node (ref "R10") (pin "2") (pinfunction "2_2") (pintype "passive"))
      (node (ref "R14") (pin "2") (pinfunction "2_2") (pintype "passive"))
      (node (ref "U1") (pin "18") (pinfunction "REFIN_18") (pintype "bidirectional"))
    )
    (net (code "46") (name "Net-(U1-RLD)") (class "Default")
      (node (ref "C2") (pin "1") (pinfunction "1_1") (pintype "passive"))
      (node (ref "R5") (pin "2") (pinfunction "2_2") (pintype "passive"))
      (node (ref "U1") (pin "5") (pinfunction "RLD_5") (pintype "bidirectional"))
    )
    (net (code "47") (name "Net-(U1-RLDFB)") (class "Default")
      (node (ref "C2") (pin "2") (pinfunction "2_2") (pintype "passive"))
      (node (ref "U1") (pin "4") (pinfunction "RLDFB_4") (pintype "bidirectional"))
    )
    (net (code "48") (name "Net-(U1-SW)") (class "Default")
      (node (ref "C6") (pin "2") (pinfunction "2_2") (pintype "passive"))
      (node (ref "R12") (pin "2") (pinfunction "2_2") (pintype "passive"))
      (node (ref "R18") (pin "2") (pinfunction "2_2") (pintype "passive"))
      (node (ref "U1") (pin "6") (pinfunction "SW_6") (pintype "bidirectional"))
    )
    (net (code "49") (name "Net-(U2-HEATSINK)") (class "Default")
      (node (ref "R40") (pin "2") (pinfunction "2_2") (pintype "passive"))
      (node (ref "U2") (pin "4") (pinfunction "HEATSINK_4") (pintype "power_in"))
    )
    (net (code "50") (name "Net-(U3-IO2)") (class "Default")
      (node (ref "R38") (pin "2") (pinfunction "2_2") (pintype "passive"))
      (node (ref "U3") (pin "24") (pinfunction "IO2_24") (pintype "bidirectional"))
    )
    (net (code "51") (name "Net-(U3-IO12)") (class "Default")
      (node (ref "U3") (pin "14") (pinfunction "IO12_14") (pintype "bidirectional"))
      (node (ref "UI") (pin "TP") (pinfunction "TP_TP") (pintype "input"))
    )
    (net (code "52") (name "Net-(U3-IO14)") (class "Default")
      (node (ref "U3") (pin "13") (pinfunction "IO14_13") (pintype "bidirectional"))
      (node (ref "UO") (pin "TP") (pinfunction "TP_TP") (pintype "input"))
    )
    (net (code "53") (name "Net-(U3-IO15)") (class "Default")
      (node (ref "R37") (pin "1") (pinfunction "1_1") (pintype "passive"))
      (node (ref "U3") (pin "23") (pinfunction "IO15_23") (pintype "bidirectional"))
    )
    (net (code "54") (name "Net-(U3-IO20)") (class "Default")
      (node (ref "U3") (pin "32") (pinfunction "IO20_32") (pintype "bidirectional"))
      (node (ref "U3") (pin "37") (pinfunction "IO23_37") (pintype "bidirectional"))
    )
    (net (code "55") (name "Net-(U3-RXD)") (class "Default")
      (node (ref "R35") (pin "1") (pinfunction "1_1") (pintype "passive"))
      (node (ref "U3") (pin "34") (pinfunction "RXD_34") (pintype "bidirectional"))
    )
    (net (code "56") (name "Net-(U3-TXD)") (class "Default")
      (node (ref "R34") (pin "1") (pinfunction "1_1") (pintype "passive"))
      (node (ref "U3") (pin "35") (pinfunction "TXD_35") (pintype "bidirectional"))
    )
    (net (code "57") (name "Net-(U4A-B)") (class "Default")
      (node (ref "R21") (pin "2") (pinfunction "2_2") (pintype "passive"))
      (node (ref "U4") (pin "2") (pinfunction "B_2") (pintype "bidirectional"))
    )
    (net (code "58") (name "RA") (class "Default")
      (node (ref "JP1") (pin "3") (pinfunction "3_3") (pintype "passive"))
      (node (ref "JP2") (pin "SLEEVE") (pinfunction "SLEEVE_SLEEVE") (pintype "bidirectional"))
      (node (ref "R2") (pin "1") (pinfunction "1_1") (pintype "passive"))
      (node (ref "R4") (pin "1") (pinfunction "1_1") (pintype "passive"))
    )
    (net (code "59") (name "REFOUT") (class "Default")
      (node (ref "C3") (pin "2") (pinfunction "2_2") (pintype "passive"))
      (node (ref "C6") (pin "1") (pinfunction "1_1") (pintype "passive"))
      (node (ref "R8") (pin "2") (pinfunction "2_2") (pintype "passive"))
      (node (ref "U1") (pin "8") (pinfunction "REFOUT_8") (pintype "bidirectional"))
    )
    (net (code "60") (name "RL") (class "Default")
      (node (ref "JP1") (pin "1") (pinfunction "1_1") (pintype "passive"))
      (node (ref "JP2") (pin "TIP") (pinfunction "LEFT_TIP") (pintype "bidirectional"))
      (node (ref "R5") (pin "1") (pinfunction "1_1") (pintype "passive"))
    )
    (net (code "61") (name "SDN") (class "Default")
      (node (ref "JP3") (pin "6") (pinfunction "6_6") (pintype "passive"))
      (node (ref "R15") (pin "1") (pinfunction "1_1") (pintype "passive"))
      (node (ref "U1") (pin "13") (pinfunction "~{SDN}_13") (pintype "bidirectional"))
    )
    (net (code "62") (name "SELECT") (class "Default")
      (node (ref "IC1") (pin "2") (pinfunction "SELECT_2") (pintype "input"))
      (node (ref "R23") (pin "2") (pinfunction "2_2") (pintype "passive"))
    )
    (net (code "63") (name "SIGNAL_OUT") (class "Default")
      (node (ref "C1") (pin "2") (pinfunction "2_2") (pintype "passive"))
      (node (ref "JP3") (pin "3") (pinfunction "3_3") (pintype "passive"))
      (node (ref "R16") (pin "2") (pinfunction "2_2") (pintype "passive"))
      (node (ref "R9") (pin "1") (pinfunction "1_1") (pintype "passive"))
      (node (ref "U1") (pin "10") (pinfunction "OUT_10") (pintype "bidirectional"))
      (node (ref "U3") (pin "6") (pinfunction "IO34_6") (pintype "bidirectional"))
    )
    (net (code "64") (name "V_REG") (class "Default")
      (node (ref "3.3V") (pin "TP") (pinfunction "TP_TP") (pintype "input"))
      (node (ref "C10") (pin "2") (pinfunction "2_2") (pintype "passive"))
      (node (ref "C13") (pin "+") (pinfunction "+_+") (pintype "passive"))
      (node (ref "C15") (pin "1") (pinfunction "1_1") (pintype "passive"))
      (node (ref "C19") (pin "1") (pinfunction "1_1") (pintype "passive"))
      (node (ref "C20") (pin "1") (pinfunction "1_1") (pintype "passive"))
      (node (ref "C21") (pin "1") (pinfunction "1_1") (pintype "passive"))
      (node (ref "C22") (pin "1") (pinfunction "1_1") (pintype "passive"))
      (node (ref "C5") (pin "2") (pinfunction "2_2") (pintype "passive"))
      (node (ref "C8") (pin "2") (pinfunction "2_2") (pintype "passive"))
      (node (ref "C9") (pin "2") (pinfunction "2_2") (pintype "passive"))
      (node (ref "IC1") (pin "5") (pinfunction "VDD_5") (pintype "power_in"))
      (node (ref "IC3") (pin "6") (pinfunction "VDD_6") (pintype "power_in"))
      (node (ref "IC3") (pin "7") (pinfunction "REGIN_7") (pintype "passive"))
      (node (ref "JP3") (pin "2") (pinfunction "2_2") (pintype "passive"))
      (node (ref "JP4") (pin "1") (pinfunction "1_1") (pintype "passive"))
      (node (ref "L1") (pin "1") (pinfunction "1_1") (pintype "passive"))
      (node (ref "R10") (pin "1") (pinfunction "1_1") (pintype "passive"))
      (node (ref "R15") (pin "2") (pinfunction "2_2") (pintype "passive"))
      (node (ref "R17") (pin "1") (pinfunction "1_1") (pintype "passive"))
      (node (ref "R20") (pin "1") (pinfunction "1_1") (pintype "passive"))
      (node (ref "R22") (pin "A") (pinfunction "A_A") (pintype "passive"))
      (node (ref "R26") (pin "2") (pinfunction "2_2") (pintype "passive"))
      (node (ref "R31") (pin "1") (pinfunction "1_1") (pintype "passive"))
      (node (ref "R39") (pin "2") (pinfunction "2_2") (pintype "passive"))
      (node (ref "R40") (pin "1") (pinfunction "1_1") (pintype "passive"))
      (node (ref "R41") (pin "2") (pinfunction "2_2") (pintype "passive"))
      (node (ref "U1") (pin "15") (pinfunction "FR_15") (pintype "bidirectional"))
      (node (ref "U1") (pin "17") (pinfunction "+VS_17") (pintype "bidirectional"))
      (node (ref "U2") (pin "2") (pinfunction "VOUT_2") (pintype "power_in"))
      (node (ref "U3") (pin "2") (pinfunction "3V3_2") (pintype "bidirectional"))
      (node (ref "U4") (pin "5") (pinfunction "P$V+_5") (pintype "bidirectional"))
    )
    (net (code "65") (name "WS") (class "Default")
      (node (ref "IC1") (pin "1") (pinfunction "WS_1") (pintype "input"))
      (node (ref "JP4") (pin "5") (pinfunction "5_5") (pintype "passive"))
      (node (ref "U3") (pin "10") (pinfunction "IO25_10") (pintype "bidirectional"))
    )
    (net (code "66") (name "unconnected-(IC3-SUSPEND-Pad12)") (class "Default")
      (node (ref "IC3") (pin "12") (pinfunction "SUSPEND_12") (pintype "output"))
    )
    (net (code "67") (name "unconnected-(IC3-~{RST}-Pad9)") (class "Default")
      (node (ref "IC3") (pin "9") (pinfunction "~{RST}_9") (pintype "bidirectional"))
    )
    (net (code "68") (name "unconnected-(IC3-~{SUSPEND}-Pad11)") (class "Default")
      (node (ref "IC3") (pin "11") (pinfunction "~{SUSPEND}_11") (pintype "output"))
    )
    (net (code "69") (name "unconnected-(P1-ID-Pad4)") (class "Default")
      (node (ref "P1") (pin "4") (pinfunction "ID_4") (pintype "passive"))
    )
    (net (code "70") (name "unconnected-(S1-S-Pad3)") (class "Default")
      (node (ref "S1") (pin "3") (pinfunction "S_3") (pintype "passive"))
    )
    (net (code "71") (name "unconnected-(U3-IO4-Pad26)") (class "Default")
      (node (ref "U3") (pin "26") (pinfunction "IO4_26") (pintype "bidirectional"))
    )
    (net (code "72") (name "unconnected-(U3-IO5-Pad29)") (class "Default")
      (node (ref "U3") (pin "29") (pinfunction "IO5_29") (pintype "bidirectional"))
    )
    (net (code "73") (name "unconnected-(U3-IO16-Pad27)") (class "Default")
      (node (ref "U3") (pin "27") (pinfunction "IO16_27") (pintype "bidirectional"))
    )
    (net (code "74") (name "unconnected-(U3-IO17-Pad28)") (class "Default")
      (node (ref "U3") (pin "28") (pinfunction "IO17_28") (pintype "bidirectional"))
    )
    (net (code "75") (name "unconnected-(U3-IO18-Pad30)") (class "Default")
      (node (ref "U3") (pin "30") (pinfunction "IO18_30") (pintype "bidirectional"))
    )
    (net (code "76") (name "unconnected-(U3-IO19-Pad31)") (class "Default")
      (node (ref "U3") (pin "31") (pinfunction "IO19_31") (pintype "bidirectional"))
    )
    (net (code "77") (name "unconnected-(U3-IO21-Pad33)") (class "Default")
      (node (ref "U3") (pin "33") (pinfunction "IO21_33") (pintype "bidirectional"))
    )
    (net (code "78") (name "unconnected-(U3-IO22-Pad36)") (class "Default")
      (node (ref "U3") (pin "36") (pinfunction "IO22_36") (pintype "bidirectional"))
    )
    (net (code "79") (name "unconnected-(U3-IO27-Pad12)") (class "Default")
      (node (ref "U3") (pin "12") (pinfunction "IO27_12") (pintype "bidirectional"))
    )
    (net (code "80") (name "unconnected-(U3-IO32-Pad8)") (class "Default")
      (node (ref "U3") (pin "8") (pinfunction "IO32_8") (pintype "bidirectional"))
    )
    (net (code "81") (name "unconnected-(U3-IO33-Pad9)") (class "Default")
      (node (ref "U3") (pin "9") (pinfunction "IO33_9") (pintype "bidirectional"))
    )
    (net (code "82") (name "unconnected-(U3-IO35-Pad7)") (class "Default")
      (node (ref "U3") (pin "7") (pinfunction "IO35_7") (pintype "bidirectional"))
    )
    (net (code "83") (name "unconnected-(U3-SCK-Pad20)") (class "Default")
      (node (ref "U3") (pin "20") (pinfunction "SCK_20") (pintype "bidirectional"))
    )
    (net (code "84") (name "unconnected-(U3-SCS-Pad19)") (class "Default")
      (node (ref "U3") (pin "19") (pinfunction "SCS_19") (pintype "bidirectional"))
    )
    (net (code "85") (name "unconnected-(U3-SDI-Pad22)") (class "Default")
      (node (ref "U3") (pin "22") (pinfunction "SDI_22") (pintype "bidirectional"))
    )
    (net (code "86") (name "unconnected-(U3-SDO-Pad21)") (class "Default")
      (node (ref "U3") (pin "21") (pinfunction "SDO_21") (pintype "bidirectional"))
    )
    (net (code "87") (name "unconnected-(U3-SENSOR_VN-Pad5)") (class "Default")
      (node (ref "U3") (pin "5") (pinfunction "SENSOR_VN_5") (pintype "bidirectional"))
    )
    (net (code "88") (name "unconnected-(U3-SENSOR_VP-Pad4)") (class "Default")
      (node (ref "U3") (pin "4") (pinfunction "SENSOR_VP_4") (pintype "bidirectional"))
    )
    (net (code "89") (name "unconnected-(U3-SHD-Pad17)") (class "Default")
      (node (ref "U3") (pin "17") (pinfunction "SHD_17") (pintype "bidirectional"))
    )
    (net (code "90") (name "unconnected-(U3-SWP-Pad18)") (class "Default")
      (node (ref "U3") (pin "18") (pinfunction "SWP_18") (pintype "bidirectional"))
    )
  )
)
